# HopeToPass-BASIC.net
KiCad netlist of a schematic drawn in EAGLE
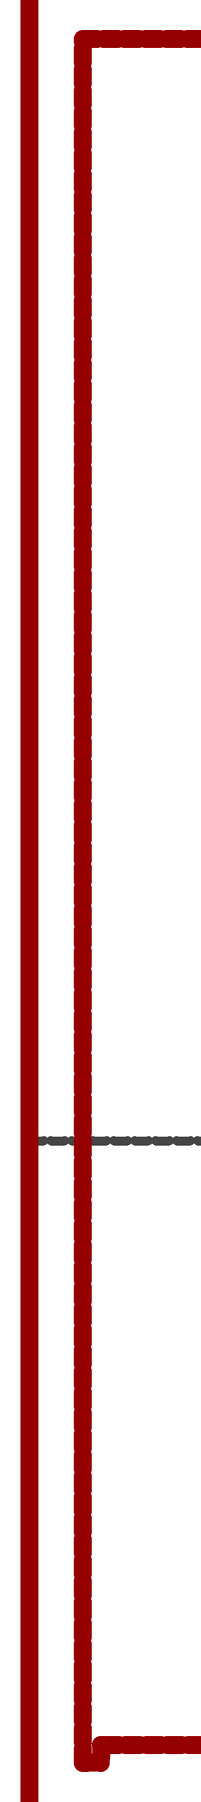
[diagram p0: schematic, sheet 1, part 1 of 2]
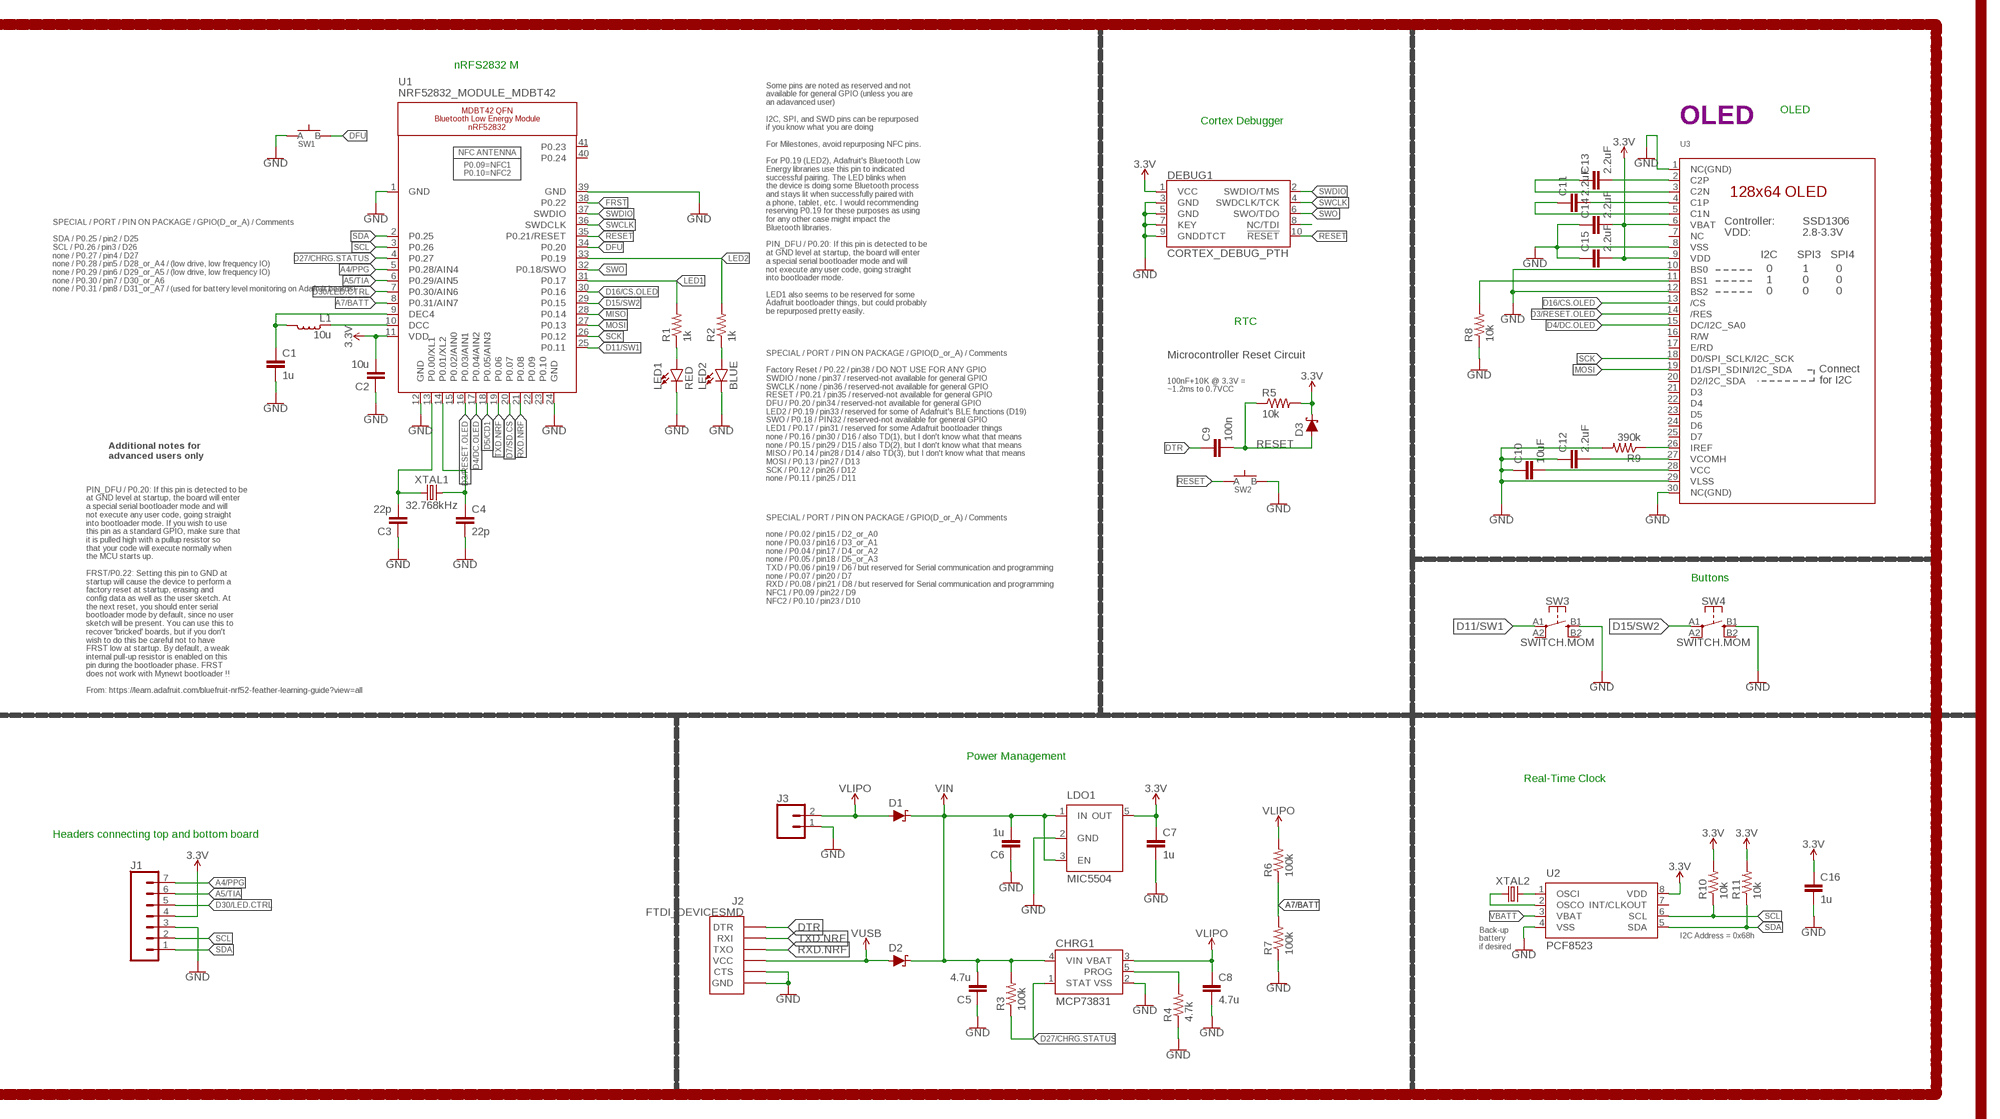
[diagram p1: schematic, sheet 1, part 2 of 2]

(export (version "E")
  (design (tool "Eeschema 10.0.6"))
  (components
    (comp (ref "C1")
      (value "1u")
      (footprint "eagle-import:C0603")
      (libsource (lib "eagle-import") (part "CAPACITOR0603"))
    )
    (comp (ref "C2")
      (value "10u")
      (footprint "eagle-import:C0805")
      (libsource (lib "eagle-import") (part "CAPACITOR0805"))
    )
    (comp (ref "C3")
      (value "22p")
      (footprint "eagle-import:C0603")
      (libsource (lib "eagle-import") (part "CAPACITOR0603"))
    )
    (comp (ref "C4")
      (value "22p")
      (footprint "eagle-import:C0603")
      (libsource (lib "eagle-import") (part "CAPACITOR0603"))
    )
    (comp (ref "C5")
      (value "4.7u")
      (footprint "eagle-import:C0603")
      (libsource (lib "eagle-import") (part "CAPACITOR0603"))
    )
    (comp (ref "C6")
      (value "1u")
      (footprint "eagle-import:C0603")
      (libsource (lib "eagle-import") (part "CAPACITOR0603"))
    )
    (comp (ref "C7")
      (value "1u")
      (footprint "eagle-import:C0603")
      (libsource (lib "eagle-import") (part "CAPACITOR0603"))
    )
    (comp (ref "C8")
      (value "4.7u")
      (footprint "eagle-import:C0603")
      (libsource (lib "eagle-import") (part "CAPACITOR0603"))
    )
    (comp (ref "C9")
      (value "100n")
      (footprint "eagle-import:C0603")
      (libsource (lib "eagle-import") (part "CAPACITOR0603"))
    )
    (comp (ref "C10")
      (value "10uF")
      (footprint "eagle-import:C0603")
      (libsource (lib "eagle-import") (part "CAPACITOR0603"))
    )
    (comp (ref "C11")
      (value "2.2uF")
      (footprint "eagle-import:C0603")
      (libsource (lib "eagle-import") (part "CAPACITOR0603"))
    )
    (comp (ref "C12")
      (value "2.2uF")
      (footprint "eagle-import:C0603")
      (libsource (lib "eagle-import") (part "CAPACITOR0603"))
    )
    (comp (ref "C13")
      (value "2.2uF")
      (footprint "eagle-import:C0603")
      (libsource (lib "eagle-import") (part "CAPACITOR0603"))
    )
    (comp (ref "C14")
      (value "2.2uF")
      (footprint "eagle-import:C0603")
      (libsource (lib "eagle-import") (part "CAPACITOR0603"))
    )
    (comp (ref "C15")
      (value "2.2uF")
      (footprint "eagle-import:C0603")
      (libsource (lib "eagle-import") (part "CAPACITOR0603"))
    )
    (comp (ref "C16")
      (value "1u")
      (footprint "eagle-import:C0603")
      (libsource (lib "eagle-import") (part "CAPACITOR0603"))
    )
    (comp (ref "CHRG1")
      (value "MCP73831")
      (footprint "eagle-import:SOT23-5")
      (libsource (lib "eagle-import") (part "MCP73831"))
    )
    (comp (ref "D1")
      (value "SCHOTTKY-USC")
      (footprint "eagle-import:USC")
      (libsource (lib "eagle-import") (part "SCHOTTKY-USC"))
    )
    (comp (ref "D2")
      (value "SCHOTTKY-USC")
      (footprint "eagle-import:USC")
      (libsource (lib "eagle-import") (part "SCHOTTKY-USC"))
    )
    (comp (ref "D3")
      (value "SCHOTTKY-USC")
      (footprint "eagle-import:USC")
      (libsource (lib "eagle-import") (part "SCHOTTKY-USC"))
    )
    (comp (ref "DEBUG1")
      (value "CORTEX_DEBUG_PTH")
      (footprint "eagle-import:2X5-PTH-1.27MM")
      (libsource (lib "eagle-import") (part "CORTEX_DEBUG_PTH"))
    )
    (comp (ref "J1")
      (value "CONN_07-1.27MM")
      (footprint "eagle-import:1X07_1.27MM")
      (libsource (lib "eagle-import") (part "CONN_07-1.27MM"))
    )
    (comp (ref "J2")
      (value "FTDI_DEVICESMD")
      (footprint "eagle-import:FTDI-SMD")
      (libsource (lib "eagle-import") (part "FTDI_DEVICESMD"))
    )
    (comp (ref "J3")
      (value "CONN_02")
      (footprint "eagle-import:1X02")
      (libsource (lib "eagle-import") (part "CONN_02"))
    )
    (comp (ref "L1")
      (value "10u")
      (footprint "eagle-import:L0603")
      (libsource (lib "eagle-import") (part "INDUCTOR0603"))
    )
    (comp (ref "LDO1")
      (value "MIC5504")
      (footprint "eagle-import:SOT23-5")
      (libsource (lib "eagle-import") (part "MIC5504"))
    )
    (comp (ref "LED1")
      (value "RED")
      (footprint "eagle-import:LED-0603")
      (libsource (lib "eagle-import") (part "LED0603"))
    )
    (comp (ref "LED2")
      (value "BLUE")
      (footprint "eagle-import:LED-0603")
      (libsource (lib "eagle-import") (part "LED0603"))
    )
    (comp (ref "R1")
      (value "1k")
      (footprint "eagle-import:R0603")
      (libsource (lib "eagle-import") (part "RESISTOR0603"))
    )
    (comp (ref "R2")
      (value "1k")
      (footprint "eagle-import:R0603")
      (libsource (lib "eagle-import") (part "RESISTOR0603"))
    )
    (comp (ref "R3")
      (value "100k")
      (footprint "eagle-import:R0603")
      (libsource (lib "eagle-import") (part "RESISTOR0603"))
    )
    (comp (ref "R4")
      (value "4.7k")
      (footprint "eagle-import:R0603")
      (libsource (lib "eagle-import") (part "RESISTOR0603"))
    )
    (comp (ref "R5")
      (value "10k")
      (footprint "eagle-import:R0603")
      (libsource (lib "eagle-import") (part "RESISTOR0603"))
    )
    (comp (ref "R6")
      (value "100k")
      (footprint "eagle-import:R0603")
      (libsource (lib "eagle-import") (part "RESISTOR0603"))
    )
    (comp (ref "R7")
      (value "100k")
      (footprint "eagle-import:R0603")
      (libsource (lib "eagle-import") (part "RESISTOR0603"))
    )
    (comp (ref "R8")
      (value "10k")
      (footprint "eagle-import:R0603")
      (libsource (lib "eagle-import") (part "RESISTOR0603"))
    )
    (comp (ref "R9")
      (value "390k")
      (footprint "eagle-import:R0603")
      (libsource (lib "eagle-import") (part "RESISTOR0603"))
    )
    (comp (ref "R10")
      (value "10k")
      (footprint "eagle-import:R0603")
      (libsource (lib "eagle-import") (part "RESISTOR0603"))
    )
    (comp (ref "R11")
      (value "10k")
      (footprint "eagle-import:R0603")
      (libsource (lib "eagle-import") (part "RESISTOR0603"))
    )
    (comp (ref "SW1")
      (value "SPST-PTS830GG140-COPY.1-3")
      (footprint "eagle-import:BUTTON-GULLWING")
      (libsource (lib "eagle-import") (part "SPST-PTS830GG140-COPY.1-3"))
    )
    (comp (ref "SW2")
      (value "SPST-PTS830GG140-COPY.1-3")
      (footprint "eagle-import:BUTTON-GULLWING")
      (libsource (lib "eagle-import") (part "SPST-PTS830GG140-COPY.1-3"))
    )
    (comp (ref "SW3")
      (value "SWITCH.MOM")
      (footprint "eagle-import:TACTILE_SWITCH_SMD_6.2MM_TALL")
      (libsource (lib "eagle-import") (part "SWITCH.MOM"))
    )
    (comp (ref "SW4")
      (value "SWITCH.MOM")
      (footprint "eagle-import:TACTILE_SWITCH_SMD_6.2MM_TALL")
      (libsource (lib "eagle-import") (part "SWITCH.MOM"))
    )
    (comp (ref "U1")
      (value "NRF52832_MODULE_MDBT42")
      (footprint "eagle-import:BLE_MODULE_RAYTAC_MDBT42")
      (libsource (lib "eagle-import") (part "NRF52832_MODULE_MDBT42"))
    )
    (comp (ref "U2")
      (value "PCF8523")
      (footprint "eagle-import:SO8")
      (libsource (lib "eagle-import") (part "PCF8523"))
    )
    (comp (ref "U3")
      (value "DISP_OLED_UG-2864HSWEG01-NO-WRAPAROUND")
      (footprint "eagle-import:UG-2864HSWEG01_0.96IN_NO-WRAPAROUND")
      (libsource (lib "eagle-import") (part "DISP_OLED_UG-2864HSWEG01-NO-WRAPAROUND"))
    )
    (comp (ref "XTAL1")
      (value "32.768kHz")
      (footprint "eagle-import:2-SMD.NOLEAD.2.0MMTO1.2MM")
      (libsource (lib "eagle-import") (part "CRYSTALECS-.327-12.5-12-C-TR"))
    )
    (comp (ref "XTAL2")
      (value "32.7680kHz")
      (footprint "eagle-import:2-SMD.NOLEAD.2.0MMTO1.2MM")
      (fields (field (name "FREQ") "32.7680KHZ"))
      (libsource (lib "eagle-import") (part "CRYSTALECS-.327-12.5-12-C-TR"))
    )
  )
  (nets
    (net (code "1") (name "3.3V") (class "Default")
      (node (ref "C14") (pin "2") (pinfunction "2_2") (pintype "passive"))
      (node (ref "C15") (pin "2") (pinfunction "2_2") (pintype "passive"))
      (node (ref "C16") (pin "1") (pinfunction "1_1") (pintype "passive"))
      (node (ref "C2") (pin "2") (pinfunction "2_2") (pintype "passive"))
      (node (ref "C7") (pin "1") (pinfunction "1_1") (pintype "passive"))
      (node (ref "D3") (pin "-") (pinfunction "C_-") (pintype "passive"))
      (node (ref "DEBUG1") (pin "1") (pinfunction "VCC_1") (pintype "bidirectional"))
      (node (ref "J1") (pin "4") (pinfunction "4_4") (pintype "passive"))
      (node (ref "LDO1") (pin "5") (pinfunction "OUT_5") (pintype "bidirectional"))
      (node (ref "R10") (pin "2") (pinfunction "2_2") (pintype "passive"))
      (node (ref "R11") (pin "2") (pinfunction "2_2") (pintype "passive"))
      (node (ref "R5") (pin "2") (pinfunction "2_2") (pintype "passive"))
      (node (ref "U1") (pin "11") (pinfunction "VDD_11") (pintype "bidirectional"))
      (node (ref "U2") (pin "8") (pinfunction "VDD_8") (pintype "power_in"))
      (node (ref "U3") (pin "6") (pinfunction "VBAT_6") (pintype "input"))
      (node (ref "U3") (pin "9") (pinfunction "VDD_9") (pintype "power_in"))
    )
    (net (code "2") (name "A4{slash}PPG") (class "Default")
      (node (ref "J1") (pin "7") (pinfunction "7_7") (pintype "passive"))
      (node (ref "U1") (pin "5") (pinfunction "P0.28/AIN4_5") (pintype "bidirectional"))
    )
    (net (code "3") (name "A5{slash}TIA") (class "Default")
      (node (ref "J1") (pin "6") (pinfunction "6_6") (pintype "passive"))
      (node (ref "U1") (pin "6") (pinfunction "P0.29/AIN5_6") (pintype "bidirectional"))
    )
    (net (code "4") (name "A7{slash}BATT") (class "Default")
      (node (ref "R6") (pin "1") (pinfunction "1_1") (pintype "passive"))
      (node (ref "R7") (pin "2") (pinfunction "2_2") (pintype "passive"))
      (node (ref "U1") (pin "8") (pinfunction "P0.31/AIN7_8") (pintype "bidirectional"))
    )
    (net (code "5") (name "D3{slash}RESET.OLED") (class "Default")
      (node (ref "U1") (pin "16") (pinfunction "P0.03/AIN1_16") (pintype "bidirectional"))
      (node (ref "U3") (pin "14") (pinfunction "/RES_14") (pintype "input"))
    )
    (net (code "6") (name "D4{slash}DC.OLED") (class "Default")
      (node (ref "U1") (pin "17") (pinfunction "P0.04/AIN2_17") (pintype "bidirectional"))
      (node (ref "U3") (pin "15") (pinfunction "DC/I2C_SA0_15") (pintype "input"))
    )
    (net (code "7") (name "D5{slash}CD1") (class "Default")
      (node (ref "U1") (pin "18") (pinfunction "P0.05/AIN3_18") (pintype "bidirectional"))
    )
    (net (code "8") (name "D7{slash}SD.CS") (class "Default")
      (node (ref "U1") (pin "20") (pinfunction "P0.07_20") (pintype "bidirectional"))
    )
    (net (code "9") (name "D11{slash}SW1") (class "Default")
      (node (ref "SW3") (pin "A1") (pinfunction "1_A1") (pintype "passive"))
      (node (ref "U1") (pin "25") (pinfunction "P0.11_25") (pintype "bidirectional"))
    )
    (net (code "10") (name "D15{slash}SW2") (class "Default")
      (node (ref "SW4") (pin "A1") (pinfunction "1_A1") (pintype "passive"))
      (node (ref "U1") (pin "29") (pinfunction "P0.15_29") (pintype "bidirectional"))
    )
    (net (code "11") (name "D16{slash}CS.OLED") (class "Default")
      (node (ref "U1") (pin "30") (pinfunction "P0.16_30") (pintype "bidirectional"))
      (node (ref "U3") (pin "13") (pinfunction "/CS_13") (pintype "input"))
    )
    (net (code "12") (name "D27{slash}CHRG.STATUS") (class "Default")
      (node (ref "CHRG1") (pin "1") (pinfunction "STAT_1") (pintype "output"))
      (node (ref "R3") (pin "1") (pinfunction "1_1") (pintype "passive"))
      (node (ref "U1") (pin "4") (pinfunction "P0.27_4") (pintype "bidirectional"))
    )
    (net (code "13") (name "D30{slash}LED.CTRL") (class "Default")
      (node (ref "J1") (pin "5") (pinfunction "5_5") (pintype "passive"))
      (node (ref "U1") (pin "7") (pinfunction "P0.30/AIN6_7") (pintype "bidirectional"))
    )
    (net (code "14") (name "DFU") (class "Default")
      (node (ref "SW1") (pin "3") (pinfunction "B_3") (pintype "bidirectional"))
      (node (ref "U1") (pin "34") (pinfunction "P0.20_34") (pintype "bidirectional"))
    )
    (net (code "15") (name "DTR") (class "Default")
      (node (ref "C9") (pin "1") (pinfunction "1_1") (pintype "passive"))
      (node (ref "J2") (pin "DTR") (pinfunction "DTR_DTR") (pintype "bidirectional"))
    )
    (net (code "16") (name "FRST") (class "Default")
      (node (ref "U1") (pin "38") (pinfunction "P0.22_38") (pintype "bidirectional"))
    )
    (net (code "17") (name "GND") (class "Default")
      (node (ref "C1") (pin "2") (pinfunction "2_2") (pintype "passive"))
      (node (ref "C10") (pin "1") (pinfunction "1_1") (pintype "passive"))
      (node (ref "C12") (pin "1") (pinfunction "1_1") (pintype "passive"))
      (node (ref "C14") (pin "1") (pinfunction "1_1") (pintype "passive"))
      (node (ref "C15") (pin "1") (pinfunction "1_1") (pintype "passive"))
      (node (ref "C16") (pin "2") (pinfunction "2_2") (pintype "passive"))
      (node (ref "C2") (pin "1") (pinfunction "1_1") (pintype "passive"))
      (node (ref "C3") (pin "1") (pinfunction "1_1") (pintype "passive"))
      (node (ref "C4") (pin "2") (pinfunction "2_2") (pintype "passive"))
      (node (ref "C5") (pin "1") (pinfunction "1_1") (pintype "passive"))
      (node (ref "C6") (pin "1") (pinfunction "1_1") (pintype "passive"))
      (node (ref "C7") (pin "2") (pinfunction "2_2") (pintype "passive"))
      (node (ref "C8") (pin "2") (pinfunction "2_2") (pintype "passive"))
      (node (ref "CHRG1") (pin "2") (pinfunction "VSS_2") (pintype "power_in"))
      (node (ref "DEBUG1") (pin "3") (pinfunction "GND_3") (pintype "bidirectional"))
      (node (ref "DEBUG1") (pin "5") (pinfunction "GND_5") (pintype "bidirectional"))
      (node (ref "DEBUG1") (pin "7") (pinfunction "KEY_7") (pintype "bidirectional"))
      (node (ref "DEBUG1") (pin "9") (pinfunction "GNDDTCT_9") (pintype "bidirectional"))
      (node (ref "J1") (pin "3") (pinfunction "3_3") (pintype "passive"))
      (node (ref "J2") (pin "CTS") (pinfunction "CTS_CTS") (pintype "bidirectional"))
      (node (ref "J2") (pin "GND") (pinfunction "GND_GND") (pintype "bidirectional"))
      (node (ref "J3") (pin "1") (pinfunction "1_1") (pintype "passive"))
      (node (ref "LDO1") (pin "2") (pinfunction "GND_2") (pintype "bidirectional"))
      (node (ref "LED1") (pin "C") (pinfunction "C_C") (pintype "passive"))
      (node (ref "LED2") (pin "C") (pinfunction "C_C") (pintype "passive"))
      (node (ref "R4") (pin "1") (pinfunction "1_1") (pintype "passive"))
      (node (ref "R7") (pin "1") (pinfunction "1_1") (pintype "passive"))
      (node (ref "R8") (pin "1") (pinfunction "1_1") (pintype "passive"))
      (node (ref "R9") (pin "2") (pinfunction "2_2") (pintype "passive"))
      (node (ref "SW1") (pin "1") (pinfunction "A_1") (pintype "bidirectional"))
      (node (ref "SW2") (pin "3") (pinfunction "B_3") (pintype "bidirectional"))
      (node (ref "SW3") (pin "B1") (pinfunction "3_B1") (pintype "passive"))
      (node (ref "SW4") (pin "B1") (pinfunction "3_B1") (pintype "passive"))
      (node (ref "U1") (pin "1") (pinfunction "GND_1") (pintype "bidirectional"))
      (node (ref "U1") (pin "12") (pinfunction "GND_12") (pintype "bidirectional"))
      (node (ref "U1") (pin "24") (pinfunction "GND_24") (pintype "bidirectional"))
      (node (ref "U1") (pin "39") (pinfunction "GND_39") (pintype "bidirectional"))
      (node (ref "U2") (pin "4") (pinfunction "VSS_4") (pintype "power_in"))
      (node (ref "U3") (pin "1") (pinfunction "NC(GND)_1") (pintype "input"))
      (node (ref "U3") (pin "10") (pinfunction "BS0_10") (pintype "input"))
      (node (ref "U3") (pin "12") (pinfunction "BS2_12") (pintype "input"))
      (node (ref "U3") (pin "29") (pinfunction "VLSS_29") (pintype "power_in"))
      (node (ref "U3") (pin "30") (pinfunction "NC(GND)_30") (pintype "input"))
      (node (ref "U3") (pin "8") (pinfunction "VSS_8") (pintype "power_in"))
    )
    (net (code "18") (name "LED1") (class "Default")
      (node (ref "R1") (pin "2") (pinfunction "2_2") (pintype "passive"))
      (node (ref "U1") (pin "31") (pinfunction "P0.17_31") (pintype "bidirectional"))
    )
    (net (code "19") (name "LED2") (class "Default")
      (node (ref "R2") (pin "2") (pinfunction "2_2") (pintype "passive"))
      (node (ref "U1") (pin "33") (pinfunction "P0.19_33") (pintype "bidirectional"))
    )
    (net (code "20") (name "MISO") (class "Default")
      (node (ref "U1") (pin "28") (pinfunction "P0.14_28") (pintype "bidirectional"))
    )
    (net (code "21") (name "MOSI") (class "Default")
      (node (ref "U1") (pin "27") (pinfunction "P0.13_27") (pintype "bidirectional"))
      (node (ref "U3") (pin "19") (pinfunction "D1/SPI_SDIN/I2C_SDA_19") (pintype "bidirectional"))
    )
    (net (code "22") (name "Net-(CHRG1-PROG)") (class "Default")
      (node (ref "CHRG1") (pin "5") (pinfunction "PROG_5") (pintype "input"))
      (node (ref "R4") (pin "2") (pinfunction "2_2") (pintype "passive"))
    )
    (net (code "23") (name "Net-(LED1-PadA)") (class "Default")
      (node (ref "LED1") (pin "A") (pinfunction "A_A") (pintype "passive"))
      (node (ref "R1") (pin "1") (pinfunction "1_1") (pintype "passive"))
    )
    (net (code "24") (name "Net-(LED2-PadA)") (class "Default")
      (node (ref "LED2") (pin "A") (pinfunction "A_A") (pintype "passive"))
      (node (ref "R2") (pin "1") (pinfunction "1_1") (pintype "passive"))
    )
    (net (code "25") (name "Net-(U1-DCC)") (class "Default")
      (node (ref "L1") (pin "1") (pinfunction "1_1") (pintype "passive"))
      (node (ref "U1") (pin "10") (pinfunction "DCC_10") (pintype "bidirectional"))
    )
    (net (code "26") (name "Net-(U1-DEC4)") (class "Default")
      (node (ref "C1") (pin "1") (pinfunction "1_1") (pintype "passive"))
      (node (ref "L1") (pin "2") (pinfunction "2_2") (pintype "passive"))
      (node (ref "U1") (pin "9") (pinfunction "DEC4_9") (pintype "bidirectional"))
    )
    (net (code "27") (name "Net-(U1-P0.00{slash}XL1)") (class "Default")
      (node (ref "C3") (pin "2") (pinfunction "2_2") (pintype "passive"))
      (node (ref "U1") (pin "13") (pinfunction "P0.00/XL1_13") (pintype "bidirectional"))
      (node (ref "XTAL1") (pin "P$1") (pinfunction "1_P$1") (pintype "passive"))
    )
    (net (code "28") (name "Net-(U1-P0.01{slash}XL2)") (class "Default")
      (node (ref "C4") (pin "1") (pinfunction "1_1") (pintype "passive"))
      (node (ref "U1") (pin "14") (pinfunction "P0.01/XL2_14") (pintype "bidirectional"))
      (node (ref "XTAL1") (pin "P$2") (pinfunction "2_P$2") (pintype "passive"))
    )
    (net (code "29") (name "Net-(U2-OSCI)") (class "Default")
      (node (ref "U2") (pin "1") (pinfunction "OSCI_1") (pintype "bidirectional"))
      (node (ref "XTAL2") (pin "P$2") (pinfunction "2_P$2") (pintype "passive"))
    )
    (net (code "30") (name "Net-(U2-OSCO)") (class "Default")
      (node (ref "U2") (pin "2") (pinfunction "OSCO_2") (pintype "bidirectional"))
      (node (ref "XTAL2") (pin "P$1") (pinfunction "1_P$1") (pintype "passive"))
    )
    (net (code "31") (name "Net-(U3-BS1)") (class "Default")
      (node (ref "R8") (pin "2") (pinfunction "2_2") (pintype "passive"))
      (node (ref "U3") (pin "11") (pinfunction "BS1_11") (pintype "input"))
    )
    (net (code "32") (name "Net-(U3-C1N)") (class "Default")
      (node (ref "C11") (pin "1") (pinfunction "1_1") (pintype "passive"))
      (node (ref "U3") (pin "5") (pinfunction "C1N_5") (pintype "input"))
    )
    (net (code "33") (name "Net-(U3-C1P)") (class "Default")
      (node (ref "C11") (pin "2") (pinfunction "2_2") (pintype "passive"))
      (node (ref "U3") (pin "4") (pinfunction "C1P_4") (pintype "input"))
    )
    (net (code "34") (name "Net-(U3-C2N)") (class "Default")
      (node (ref "C13") (pin "1") (pinfunction "1_1") (pintype "passive"))
      (node (ref "U3") (pin "3") (pinfunction "C2N_3") (pintype "input"))
    )
    (net (code "35") (name "Net-(U3-C2P)") (class "Default")
      (node (ref "C13") (pin "2") (pinfunction "2_2") (pintype "passive"))
      (node (ref "U3") (pin "2") (pinfunction "C2P_2") (pintype "input"))
    )
    (net (code "36") (name "Net-(U3-IREF)") (class "Default")
      (node (ref "R9") (pin "1") (pinfunction "1_1") (pintype "passive"))
      (node (ref "U3") (pin "26") (pinfunction "IREF_26") (pintype "input"))
    )
    (net (code "37") (name "Net-(U3-VCC)") (class "Default")
      (node (ref "C10") (pin "2") (pinfunction "2_2") (pintype "passive"))
      (node (ref "U3") (pin "28") (pinfunction "VCC_28") (pintype "power_in"))
    )
    (net (code "38") (name "Net-(U3-VCOMH)") (class "Default")
      (node (ref "C12") (pin "2") (pinfunction "2_2") (pintype "passive"))
      (node (ref "U3") (pin "27") (pinfunction "VCOMH_27") (pintype "output"))
    )
    (net (code "39") (name "RESET") (class "Default")
      (node (ref "C9") (pin "2") (pinfunction "2_2") (pintype "passive"))
      (node (ref "D3") (pin "+") (pinfunction "A_+") (pintype "passive"))
      (node (ref "DEBUG1") (pin "10") (pinfunction "~{RESET}_10") (pintype "bidirectional"))
      (node (ref "R5") (pin "1") (pinfunction "1_1") (pintype "passive"))
      (node (ref "SW2") (pin "1") (pinfunction "A_1") (pintype "bidirectional"))
      (node (ref "U1") (pin "35") (pinfunction "P0.21/RESET_35") (pintype "bidirectional"))
    )
    (net (code "40") (name "RXD.NRF") (class "Default")
      (node (ref "J2") (pin "TXO") (pinfunction "TXO_TXO") (pintype "bidirectional"))
      (node (ref "U1") (pin "21") (pinfunction "P0.08_21") (pintype "bidirectional"))
    )
    (net (code "41") (name "SCK") (class "Default")
      (node (ref "U1") (pin "26") (pinfunction "P0.12_26") (pintype "bidirectional"))
      (node (ref "U3") (pin "18") (pinfunction "D0/SPI_SCLK/I2C_SCK_18") (pintype "bidirectional"))
    )
    (net (code "42") (name "SCL") (class "Default")
      (node (ref "J1") (pin "2") (pinfunction "2_2") (pintype "passive"))
      (node (ref "R10") (pin "1") (pinfunction "1_1") (pintype "passive"))
      (node (ref "U1") (pin "3") (pinfunction "P0.26_3") (pintype "bidirectional"))
      (node (ref "U2") (pin "6") (pinfunction "SCL_6") (pintype "bidirectional"))
    )
    (net (code "43") (name "SDA") (class "Default")
      (node (ref "J1") (pin "1") (pinfunction "1_1") (pintype "passive"))
      (node (ref "R11") (pin "1") (pinfunction "1_1") (pintype "passive"))
      (node (ref "U1") (pin "2") (pinfunction "P0.25_2") (pintype "bidirectional"))
      (node (ref "U2") (pin "5") (pinfunction "SDA_5") (pintype "bidirectional"))
    )
    (net (code "44") (name "SWCLK") (class "Default")
      (node (ref "DEBUG1") (pin "4") (pinfunction "SWDCLK/TCK_4") (pintype "bidirectional"))
      (node (ref "U1") (pin "36") (pinfunction "SWDCLK_36") (pintype "bidirectional"))
    )
    (net (code "45") (name "SWDIO") (class "Default")
      (node (ref "DEBUG1") (pin "2") (pinfunction "SWDIO/TMS_2") (pintype "bidirectional"))
      (node (ref "U1") (pin "37") (pinfunction "SWDIO_37") (pintype "bidirectional"))
    )
    (net (code "46") (name "SWO") (class "Default")
      (node (ref "DEBUG1") (pin "6") (pinfunction "SWO/TDO_6") (pintype "bidirectional"))
      (node (ref "U1") (pin "32") (pinfunction "P0.18/SWO_32") (pintype "bidirectional"))
    )
    (net (code "47") (name "TXD.NRF") (class "Default")
      (node (ref "J2") (pin "RXI") (pinfunction "RXI_RXI") (pintype "bidirectional"))
      (node (ref "U1") (pin "19") (pinfunction "P0.06_19") (pintype "bidirectional"))
    )
    (net (code "48") (name "VBATT") (class "Default")
      (node (ref "U2") (pin "3") (pinfunction "VBAT_3") (pintype "power_in"))
    )
    (net (code "49") (name "VIN") (class "Default")
      (node (ref "C5") (pin "2") (pinfunction "2_2") (pintype "passive"))
      (node (ref "C6") (pin "2") (pinfunction "2_2") (pintype "passive"))
      (node (ref "CHRG1") (pin "4") (pinfunction "VIN_4") (pintype "power_in"))
      (node (ref "D1") (pin "-") (pinfunction "C_-") (pintype "passive"))
      (node (ref "D2") (pin "-") (pinfunction "C_-") (pintype "passive"))
      (node (ref "LDO1") (pin "1") (pinfunction "IN_1") (pintype "bidirectional"))
      (node (ref "LDO1") (pin "3") (pinfunction "EN_3") (pintype "bidirectional"))
      (node (ref "R3") (pin "2") (pinfunction "2_2") (pintype "passive"))
    )
    (net (code "50") (name "VLIPO") (class "Default")
      (node (ref "C8") (pin "1") (pinfunction "1_1") (pintype "passive"))
      (node (ref "CHRG1") (pin "3") (pinfunction "VBAT_3") (pintype "power_in"))
      (node (ref "D1") (pin "+") (pinfunction "A_+") (pintype "passive"))
      (node (ref "J3") (pin "2") (pinfunction "2_2") (pintype "passive"))
      (node (ref "R6") (pin "2") (pinfunction "2_2") (pintype "passive"))
    )
    (net (code "51") (name "VUSB") (class "Default")
      (node (ref "D2") (pin "+") (pinfunction "A_+") (pintype "passive"))
      (node (ref "J2") (pin "VCC") (pinfunction "VCC_VCC") (pintype "bidirectional"))
    )
    (net (code "52") (name "unconnected-(DEBUG1-NC{slash}TDI-Pad8)") (class "Default")
      (node (ref "DEBUG1") (pin "8") (pinfunction "NC/TDI_8") (pintype "bidirectional"))
    )
    (net (code "53") (name "unconnected-(SW3-2-PadA2)") (class "Default")
      (node (ref "SW3") (pin "A2") (pinfunction "2_A2") (pintype "passive"))
    )
    (net (code "54") (name "unconnected-(SW3-4-PadB2)") (class "Default")
      (node (ref "SW3") (pin "B2") (pinfunction "4_B2") (pintype "passive"))
    )
    (net (code "55") (name "unconnected-(SW4-2-PadA2)") (class "Default")
      (node (ref "SW4") (pin "A2") (pinfunction "2_A2") (pintype "passive"))
    )
    (net (code "56") (name "unconnected-(SW4-4-PadB2)") (class "Default")
      (node (ref "SW4") (pin "B2") (pinfunction "4_B2") (pintype "passive"))
    )
    (net (code "57") (name "unconnected-(U1-P0.02{slash}AIN0-Pad15)") (class "Default")
      (node (ref "U1") (pin "15") (pinfunction "P0.02/AIN0_15") (pintype "bidirectional"))
    )
    (net (code "58") (name "unconnected-(U1-P0.09-Pad22)") (class "Default")
      (node (ref "U1") (pin "22") (pinfunction "P0.09_22") (pintype "bidirectional"))
    )
    (net (code "59") (name "unconnected-(U1-P0.10-Pad23)") (class "Default")
      (node (ref "U1") (pin "23") (pinfunction "P0.10_23") (pintype "bidirectional"))
    )
    (net (code "60") (name "unconnected-(U1-P0.23-Pad41)") (class "Default")
      (node (ref "U1") (pin "41") (pinfunction "P0.23_41") (pintype "bidirectional"))
    )
    (net (code "61") (name "unconnected-(U1-P0.24-Pad40)") (class "Default")
      (node (ref "U1") (pin "40") (pinfunction "P0.24_40") (pintype "bidirectional"))
    )
    (net (code "62") (name "unconnected-(U2-INT{slash}CLKOUT-Pad7)") (class "Default")
      (node (ref "U2") (pin "7") (pinfunction "INT/CLKOUT_7") (pintype "bidirectional"))
    )
    (net (code "63") (name "unconnected-(U3-D2{slash}I2C_SDA-Pad20)") (class "Default")
      (node (ref "U3") (pin "20") (pinfunction "D2/I2C_SDA_20") (pintype "bidirectional"))
    )
    (net (code "64") (name "unconnected-(U3-D3-Pad21)") (class "Default")
      (node (ref "U3") (pin "21") (pinfunction "D3_21") (pintype "bidirectional"))
    )
    (net (code "65") (name "unconnected-(U3-D4-Pad22)") (class "Default")
      (node (ref "U3") (pin "22") (pinfunction "D4_22") (pintype "bidirectional"))
    )
    (net (code "66") (name "unconnected-(U3-D5-Pad23)") (class "Default")
      (node (ref "U3") (pin "23") (pinfunction "D5_23") (pintype "bidirectional"))
    )
    (net (code "67") (name "unconnected-(U3-D6-Pad24)") (class "Default")
      (node (ref "U3") (pin "24") (pinfunction "D6_24") (pintype "bidirectional"))
    )
    (net (code "68") (name "unconnected-(U3-D7-Pad25)") (class "Default")
      (node (ref "U3") (pin "25") (pinfunction "D7_25") (pintype "bidirectional"))
    )
    (net (code "69") (name "unconnected-(U3-E{slash}RD-Pad17)") (class "Default")
      (node (ref "U3") (pin "17") (pinfunction "E/RD_17") (pintype "input"))
    )
    (net (code "70") (name "unconnected-(U3-NC-Pad7)") (class "Default")
      (node (ref "U3") (pin "7") (pinfunction "NC_7") (pintype "no_connect"))
    )
    (net (code "71") (name "unconnected-(U3-R{slash}W-Pad16)") (class "Default")
      (node (ref "U3") (pin "16") (pinfunction "R/W_16") (pintype "input"))
    )
  )
)
